# 3_power.net
KiCad netlist of a schematic drawn in Altium Designer
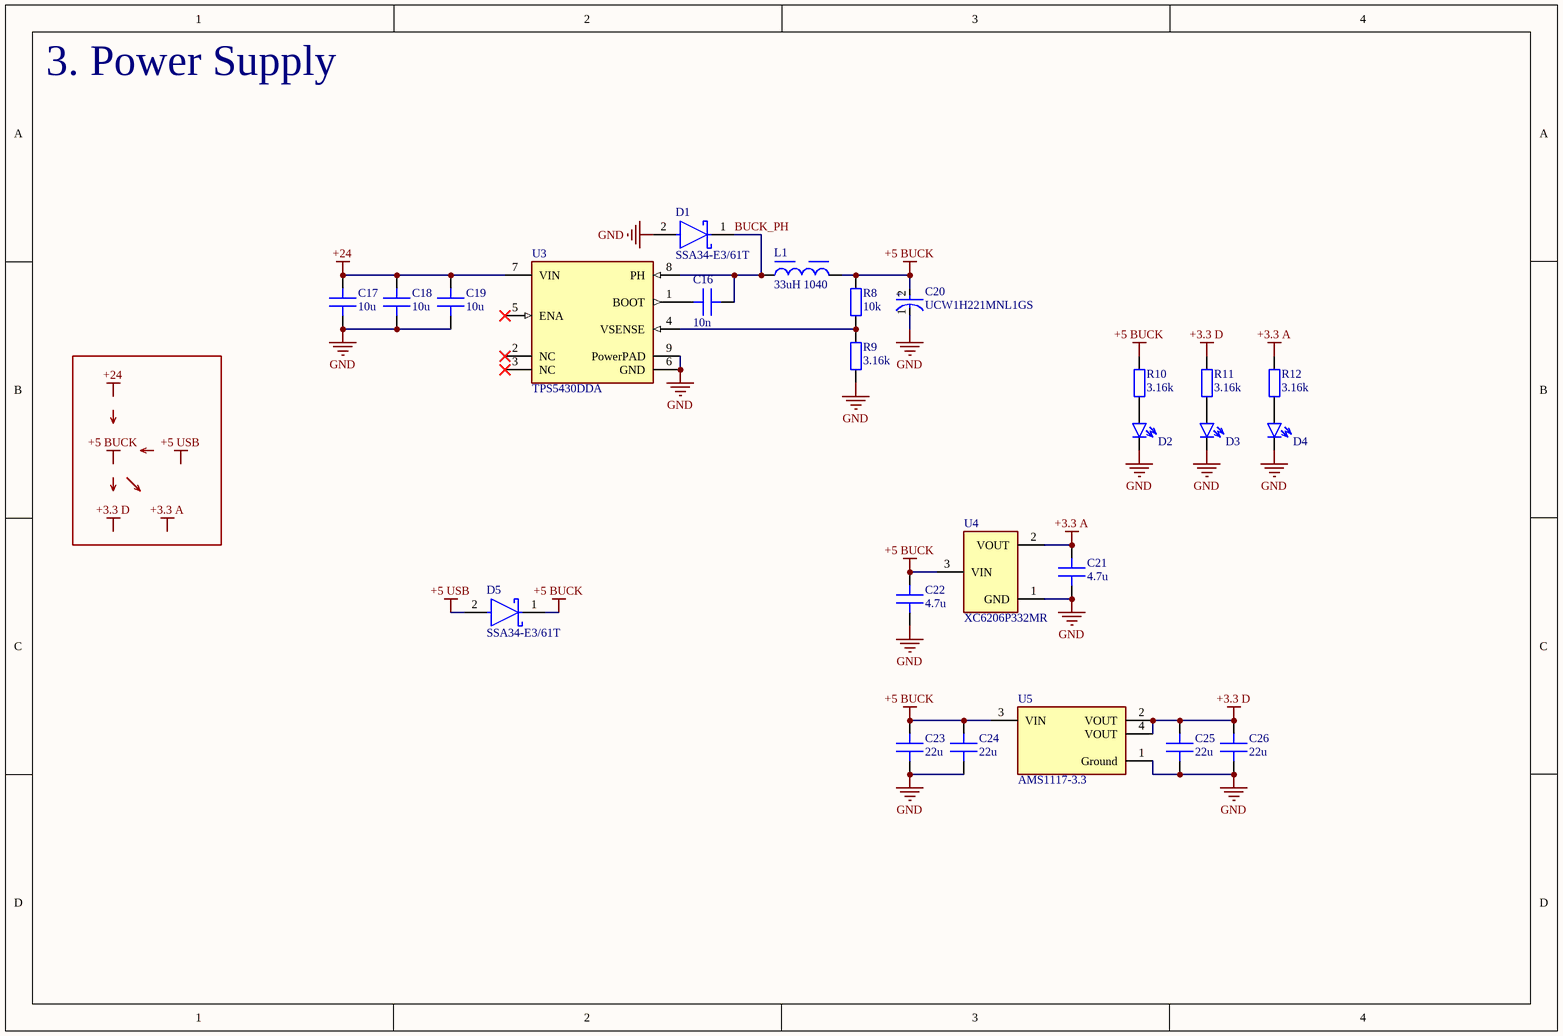
[diagram p0: 3_power.SchDoc]

(export (version "E")
  (design (tool "Eeschema 10.0.6"))
  (components
    (comp (ref "C16")
      (value "10n")
      (footprint "IPC C C0402 NO SILK")
      (libsource (lib "JLCPCB Library") (part "Generic CAP 0402"))
    )
    (comp (ref "C17")
      (value "10u")
      (footprint "IPC C C1210 NO SILK")
      (libsource (lib "JLCPCB Library") (part "Generic CAP 1210"))
    )
    (comp (ref "C18")
      (value "10u")
      (footprint "IPC C C1210 NO SILK")
      (libsource (lib "JLCPCB Library") (part "Generic CAP 1210"))
    )
    (comp (ref "C19")
      (value "10u")
      (footprint "IPC C C1210 NO SILK")
      (libsource (lib "JLCPCB Library") (part "Generic CAP 1210"))
    )
    (comp (ref "C20")
      (value "UCW1H221MNL1GS")
      (footprint "FP-UCW1H221MNL1GS-MFG")
      (description "CAP ALUM 220UF 20% 50V SMD")
      (fields (field (name "TOLERANCE") "20%") (field (name "VOLTAGE") "50V"))
      (libsource (lib "Altium Content Vault") (part "cf48714ba7e38822c1575c7ec0b6d1f"))
    )
    (comp (ref "C21")
      (value "4.7u")
      (footprint "IPC C C0603 NO SILK")
      (libsource (lib "JLCPCB Library") (part "Generic CAP 0603"))
    )
    (comp (ref "C22")
      (value "4.7u")
      (footprint "IPC C C0603 NO SILK")
      (libsource (lib "JLCPCB Library") (part "Generic CAP 0603"))
    )
    (comp (ref "C23")
      (value "22u")
      (footprint "IPC C C0603 NO SILK")
      (libsource (lib "JLCPCB Library") (part "Generic CAP 0603"))
    )
    (comp (ref "C24")
      (value "22u")
      (footprint "IPC C C0603 NO SILK")
      (libsource (lib "JLCPCB Library") (part "Generic CAP 0603"))
    )
    (comp (ref "C25")
      (value "22u")
      (footprint "IPC C C0603 NO SILK")
      (libsource (lib "JLCPCB Library") (part "Generic CAP 0603"))
    )
    (comp (ref "C26")
      (value "22u")
      (footprint "IPC C C0603 NO SILK")
      (libsource (lib "JLCPCB Library") (part "Generic CAP 0603"))
    )
    (comp (ref "D1")
      (value "SSA34-E3/61T")
      (footprint "FP-95400-MFG")
      (description "DIODE SCHOTTKY 40V 3A DO214AC")
      (libsource (lib "Altium Content Vault") (part "1d6ec82d83fb6aee721767c19dac4b9"))
    )
    (comp (ref "D2")
      (value "Red LED 0603")
      (footprint "IPC C D0603")
      (libsource (lib "JLCPCB Library") (part "Generic LED 0603"))
    )
    (comp (ref "D3")
      (value "Yellow LED 0603")
      (footprint "IPC C D0603")
      (libsource (lib "JLCPCB Library") (part "Generic LED 0603"))
    )
    (comp (ref "D4")
      (value "Yellow LED 0603")
      (footprint "IPC C D0603")
      (libsource (lib "JLCPCB Library") (part "Generic LED 0603"))
    )
    (comp (ref "D5")
      (value "SSA34-E3/61T")
      (footprint "FP-95400-MFG")
      (description "DIODE SCHOTTKY 40V 3A DO214AC")
      (libsource (lib "Altium Content Vault") (part "1d6ec82d83fb6aee721767c19dac4b9"))
    )
    (comp (ref "L1")
      (value "33uH 1040")
      (footprint "WE-LHMI_1040")
      (libsource (lib "Altium Content Vault") (part "Inductor - 3"))
    )
    (comp (ref "R8")
      (value "10k")
      (footprint "IPC C R0402 NO SILK")
      (libsource (lib "JLCPCB Library") (part "Generic RES 0402"))
    )
    (comp (ref "R9")
      (value "3.16k")
      (footprint "IPC C R0402 NO SILK")
      (libsource (lib "JLCPCB Library") (part "Generic RES 0402"))
    )
    (comp (ref "R10")
      (value "3.16k")
      (footprint "IPC C R0402 NO SILK")
      (libsource (lib "JLCPCB Library") (part "Generic RES 0402"))
    )
    (comp (ref "R11")
      (value "3.16k")
      (footprint "IPC C R0402 NO SILK")
      (libsource (lib "JLCPCB Library") (part "Generic RES 0402"))
    )
    (comp (ref "R12")
      (value "3.16k")
      (footprint "IPC C R0402 NO SILK")
      (libsource (lib "JLCPCB Library") (part "Generic RES 0402"))
    )
    (comp (ref "U3")
      (value "TPS5430DDA")
      (footprint "FP-DDA0008J-MFG")
      (description "IC REG BUCK ADJUSTABLE 3A 8SOPWR")
      (fields
        (field (name "MANUFACTURER") "Texas Instruments")
        (field (name "OCTOPART") "https://octopart.com/tps5430dda-texas+instruments-589977")
      )
      (libsource (lib "Altium Content Vault") (part "98da629940cea6febc5630bb55159f3"))
    )
    (comp (ref "U4")
      (value "XC6206P332MR")
      (footprint "SOT23-3")
      (fields (field (name "MANUFACTURER") "TOREX(特瑞仕)"))
      (libsource (lib "JLCPCB Library") (part "3.3V Regulator XC6206P332MR_C5446"))
    )
    (comp (ref "U5")
      (value "AMS1117-3.3")
      (footprint "FP-AMS1117-IPC_C")
      (description "LDO Voltage Regulators 1A, 3.3V")
      (fields
        (field (name "OCTOPART") "https://octopart.com/ams1117-3.3-advanced+monolithic+systems-25899300")
        (field (name "MANUFACTURER") "Advanced Monolithic Systems")
      )
      (libsource (lib "Altium Content Vault") (part "8bdbb5f8e77002000e30dd2845d0354"))
    )
  )
  (nets
    (net (code "1") (name "+3.3 A") (class "Default")
      (node (ref "C21") (pin "2") (pinfunction "2_2") (pintype "passive"))
      (node (ref "R12") (pin "2") (pinfunction "2_2") (pintype "passive"))
      (node (ref "U4") (pin "2") (pinfunction "VOUT_2") (pintype "power_in"))
    )
    (net (code "2") (name "+3.3 D") (class "Default")
      (node (ref "C25") (pin "2") (pinfunction "2_2") (pintype "passive"))
      (node (ref "C26") (pin "2") (pinfunction "2_2") (pintype "passive"))
      (node (ref "R11") (pin "2") (pinfunction "2_2") (pintype "passive"))
      (node (ref "U5") (pin "2") (pinfunction "VOUT_2") (pintype "passive"))
      (node (ref "U5") (pin "4") (pinfunction "VOUT_4") (pintype "passive"))
    )
    (net (code "3") (name "+5 BUCK") (class "Default")
      (node (ref "C20") (pin "2") (pinfunction "A_2") (pintype "passive"))
      (node (ref "C22") (pin "2") (pinfunction "2_2") (pintype "passive"))
      (node (ref "C23") (pin "2") (pinfunction "2_2") (pintype "passive"))
      (node (ref "C24") (pin "2") (pinfunction "2_2") (pintype "passive"))
      (node (ref "D5") (pin "1") (pinfunction "C_1") (pintype "passive"))
      (node (ref "L1") (pin "2") (pinfunction "2_2") (pintype "passive"))
      (node (ref "R10") (pin "2") (pinfunction "2_2") (pintype "passive"))
      (node (ref "R8") (pin "2") (pinfunction "2_2") (pintype "passive"))
      (node (ref "U4") (pin "3") (pinfunction "VIN_3") (pintype "power_in"))
      (node (ref "U5") (pin "3") (pinfunction "VIN_3") (pintype "power_in"))
    )
    (net (code "4") (name "+5 USB") (class "Default")
      (node (ref "D5") (pin "2") (pinfunction "A_2") (pintype "passive"))
    )
    (net (code "5") (name "+24") (class "Default")
      (node (ref "C17") (pin "1") (pinfunction "1_1") (pintype "passive"))
      (node (ref "C18") (pin "1") (pinfunction "1_1") (pintype "passive"))
      (node (ref "C19") (pin "1") (pinfunction "1_1") (pintype "passive"))
      (node (ref "U3") (pin "7") (pinfunction "VIN_7") (pintype "power_in"))
    )
    (net (code "6") (name "/BUCK_PH") (class "Default")
      (node (ref "C16") (pin "2") (pinfunction "2_2") (pintype "passive"))
      (node (ref "D1") (pin "1") (pinfunction "C_1") (pintype "passive"))
      (node (ref "L1") (pin "1") (pinfunction "1_1") (pintype "passive"))
      (node (ref "U3") (pin "8") (pinfunction "PH_8") (pintype "input"))
    )
    (net (code "7") (name "GND") (class "Default")
      (node (ref "C17") (pin "2") (pinfunction "2_2") (pintype "passive"))
      (node (ref "C18") (pin "2") (pinfunction "2_2") (pintype "passive"))
      (node (ref "C19") (pin "2") (pinfunction "2_2") (pintype "passive"))
      (node (ref "C20") (pin "1") (pinfunction "C_1") (pintype "passive"))
      (node (ref "C21") (pin "1") (pinfunction "1_1") (pintype "passive"))
      (node (ref "C22") (pin "1") (pinfunction "1_1") (pintype "passive"))
      (node (ref "C23") (pin "1") (pinfunction "1_1") (pintype "passive"))
      (node (ref "C24") (pin "1") (pinfunction "1_1") (pintype "passive"))
      (node (ref "C25") (pin "1") (pinfunction "1_1") (pintype "passive"))
      (node (ref "C26") (pin "1") (pinfunction "1_1") (pintype "passive"))
      (node (ref "D1") (pin "2") (pinfunction "A_2") (pintype "passive"))
      (node (ref "D2") (pin "2") (pinfunction "C_2") (pintype "passive"))
      (node (ref "D3") (pin "2") (pinfunction "C_2") (pintype "passive"))
      (node (ref "D4") (pin "2") (pinfunction "C_2") (pintype "passive"))
      (node (ref "R9") (pin "1") (pinfunction "1_1") (pintype "passive"))
      (node (ref "U3") (pin "6") (pinfunction "GND_6") (pintype "power_in"))
      (node (ref "U3") (pin "9") (pinfunction "PowerPAD_9") (pintype "power_in"))
      (node (ref "U4") (pin "1") (pinfunction "GND_1") (pintype "power_in"))
      (node (ref "U5") (pin "1") (pinfunction "Ground_1") (pintype "power_in"))
    )
    (net (code "8") (name "Net-(D2-A)") (class "Default")
      (node (ref "D2") (pin "1") (pinfunction "A_1") (pintype "passive"))
      (node (ref "R10") (pin "1") (pinfunction "1_1") (pintype "passive"))
    )
    (net (code "9") (name "Net-(D3-A)") (class "Default")
      (node (ref "D3") (pin "1") (pinfunction "A_1") (pintype "passive"))
      (node (ref "R11") (pin "1") (pinfunction "1_1") (pintype "passive"))
    )
    (net (code "10") (name "Net-(D4-A)") (class "Default")
      (node (ref "D4") (pin "1") (pinfunction "A_1") (pintype "passive"))
      (node (ref "R12") (pin "1") (pinfunction "1_1") (pintype "passive"))
    )
    (net (code "11") (name "Net-(U3-BOOT)") (class "Default")
      (node (ref "C16") (pin "1") (pinfunction "1_1") (pintype "passive"))
      (node (ref "U3") (pin "1") (pinfunction "BOOT_1") (pintype "output"))
    )
    (net (code "12") (name "Net-(U3-VSENSE)") (class "Default")
      (node (ref "R8") (pin "1") (pinfunction "1_1") (pintype "passive"))
      (node (ref "R9") (pin "2") (pinfunction "2_2") (pintype "passive"))
      (node (ref "U3") (pin "4") (pinfunction "VSENSE_4") (pintype "input"))
    )
    (net (code "13") (name "unconnected-(U3-ENA-Pad5)") (class "Default")
      (node (ref "U3") (pin "5") (pinfunction "ENA_5") (pintype "input+no_connect"))
    )
    (net (code "14") (name "unconnected-(U3-NC-Pad2)") (class "Default")
      (node (ref "U3") (pin "2") (pinfunction "NC_2") (pintype "passive+no_connect"))
    )
    (net (code "15") (name "unconnected-(U3-NC-Pad3)") (class "Default")
      (node (ref "U3") (pin "3") (pinfunction "NC_3") (pintype "passive+no_connect"))
    )
  )
)
